# brick_analog_led_smd.net
KiCad netlist of a schematic drawn in EAGLE
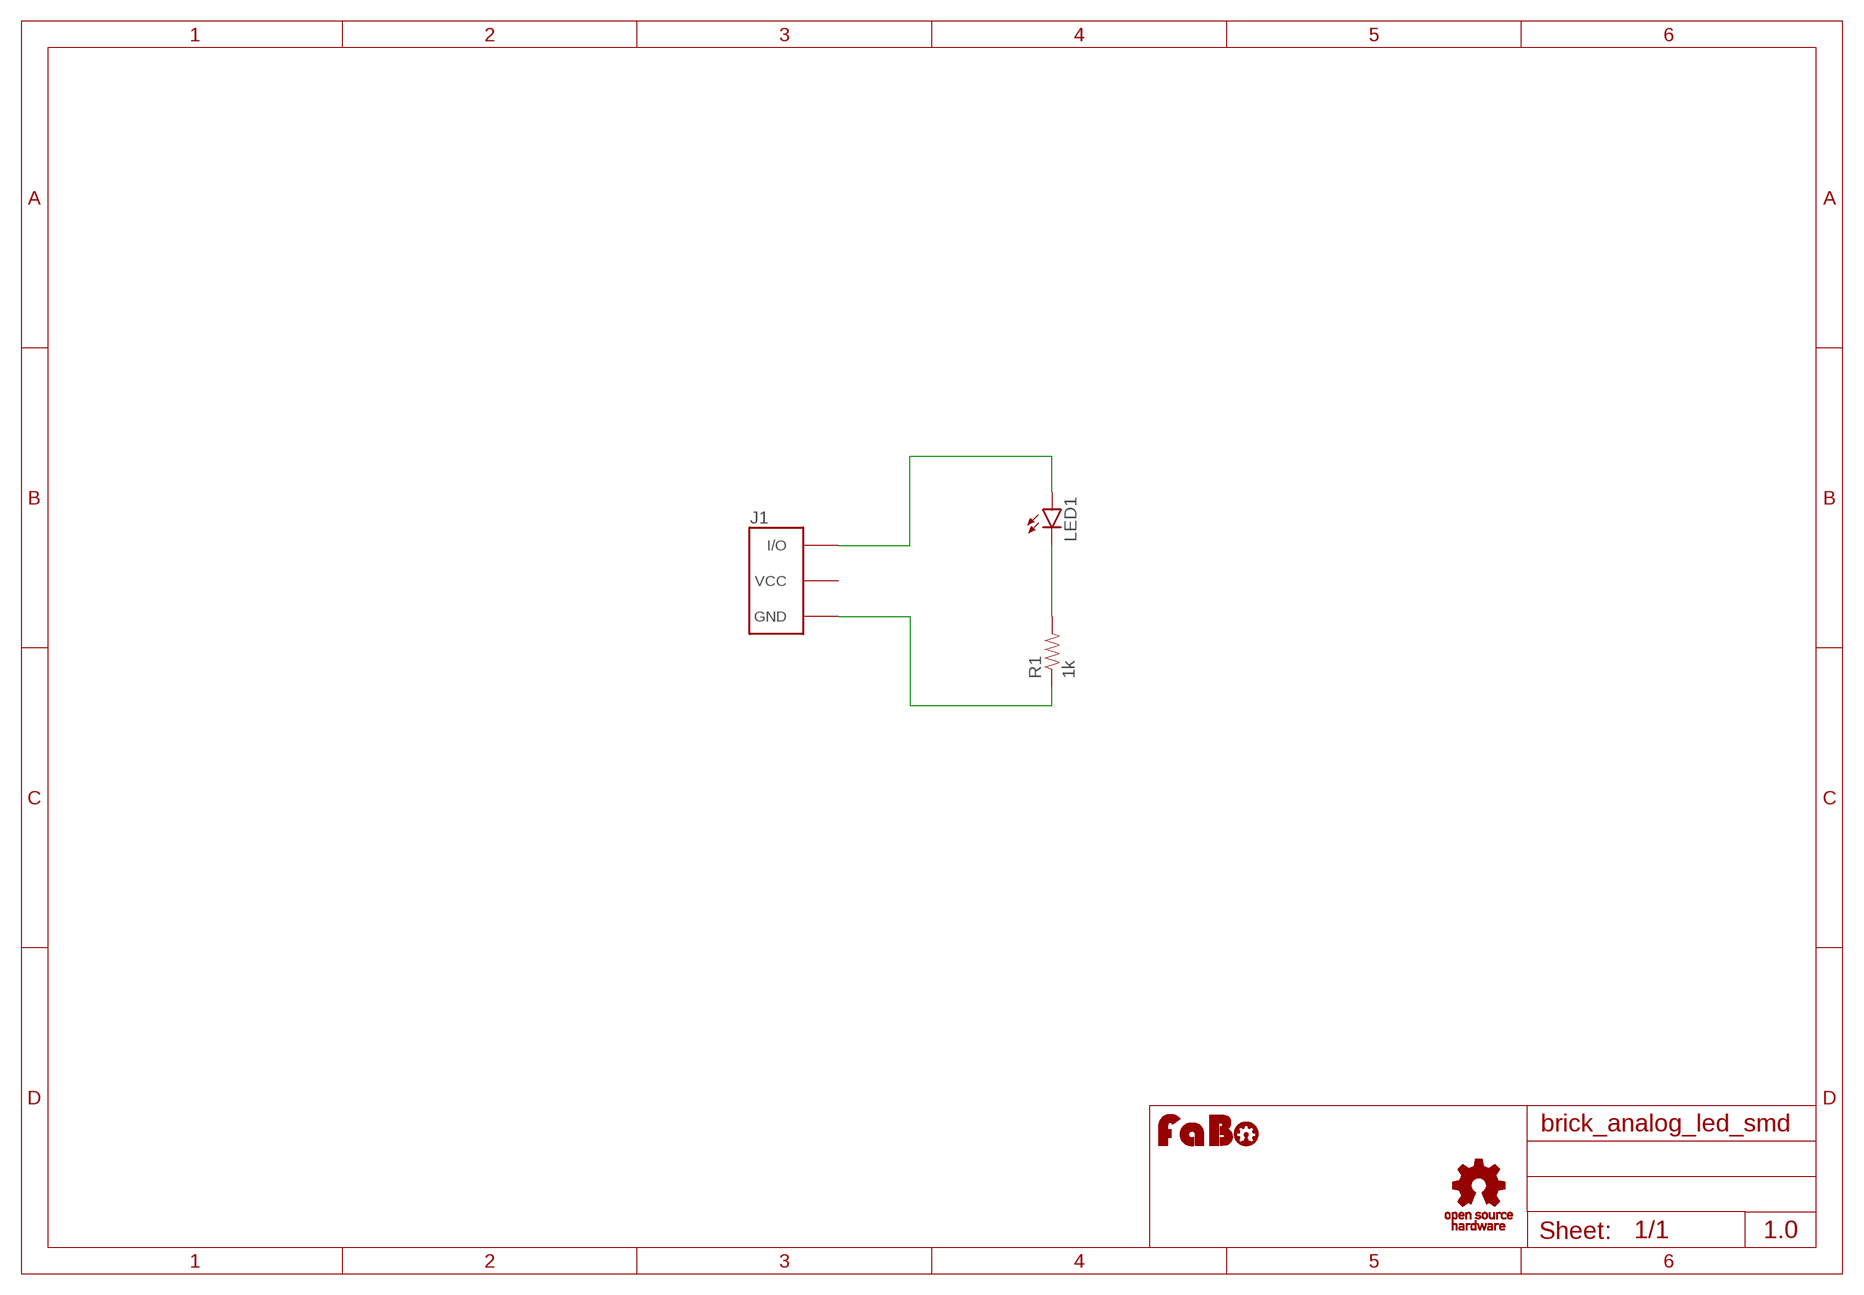
[diagram p0: schematic, sheet 1]

(export (version "E")
  (design (tool "Eeschema 10.0.6"))
  (components
    (comp (ref "J1")
      (value "BRICK_3PIN_NORMAL")
      (footprint "eagle-import:BRICK_3PIN")
      (libsource (lib "eagle-import") (part "BRICK_3PIN_NORMAL"))
    )
    (comp (ref "LED1")
      (value "LED-EIA0603")
      (footprint "eagle-import:EIA0603-LED")
      (libsource (lib "eagle-import") (part "LED-EIA0603"))
    )
    (comp (ref "R1")
      (value "1k")
      (footprint "eagle-import:EIA0603")
      (libsource (lib "eagle-import") (part "RES-EIA0603"))
    )
    (comp (ref "U$2")
      (value "LOGO_FABO-M")
      (footprint "eagle-import:LOGO_FABO_M")
      (libsource (lib "eagle-import") (part "LOGO_FABO-M"))
    )
    (comp (ref "U$4")
      (value "LOGO_OSHW_T-M")
      (footprint "eagle-import:LOGO_OSHW_T_M")
      (libsource (lib "eagle-import") (part "LOGO_OSHW_T-M"))
    )
  )
  (nets
    (net (code "1") (name "Net-(J1-I{slash}O)") (class "Default")
      (node (ref "J1") (pin "IN/OUT") (pinfunction "I/O_IN/OUT") (pintype "bidirectional"))
      (node (ref "LED1") (pin "A") (pinfunction "A_A") (pintype "passive"))
    )
    (net (code "2") (name "Net-(J1-PadGND)") (class "Default")
      (node (ref "J1") (pin "GND") (pinfunction "GND_GND") (pintype "bidirectional"))
      (node (ref "R1") (pin "1") (pinfunction "1_1") (pintype "passive"))
    )
    (net (code "3") (name "Net-(LED1-PadC)") (class "Default")
      (node (ref "LED1") (pin "C") (pinfunction "C_C") (pintype "passive"))
      (node (ref "R1") (pin "2") (pinfunction "2_2") (pintype "passive"))
    )
    (net (code "4") (name "unconnected-(J1-PadVCC)") (class "Default")
      (node (ref "J1") (pin "VCC") (pinfunction "VCC_VCC") (pintype "bidirectional"))
    )
  )
)
